# Ethernet_PHY.net
KiCad netlist of a schematic drawn in Altium Designer
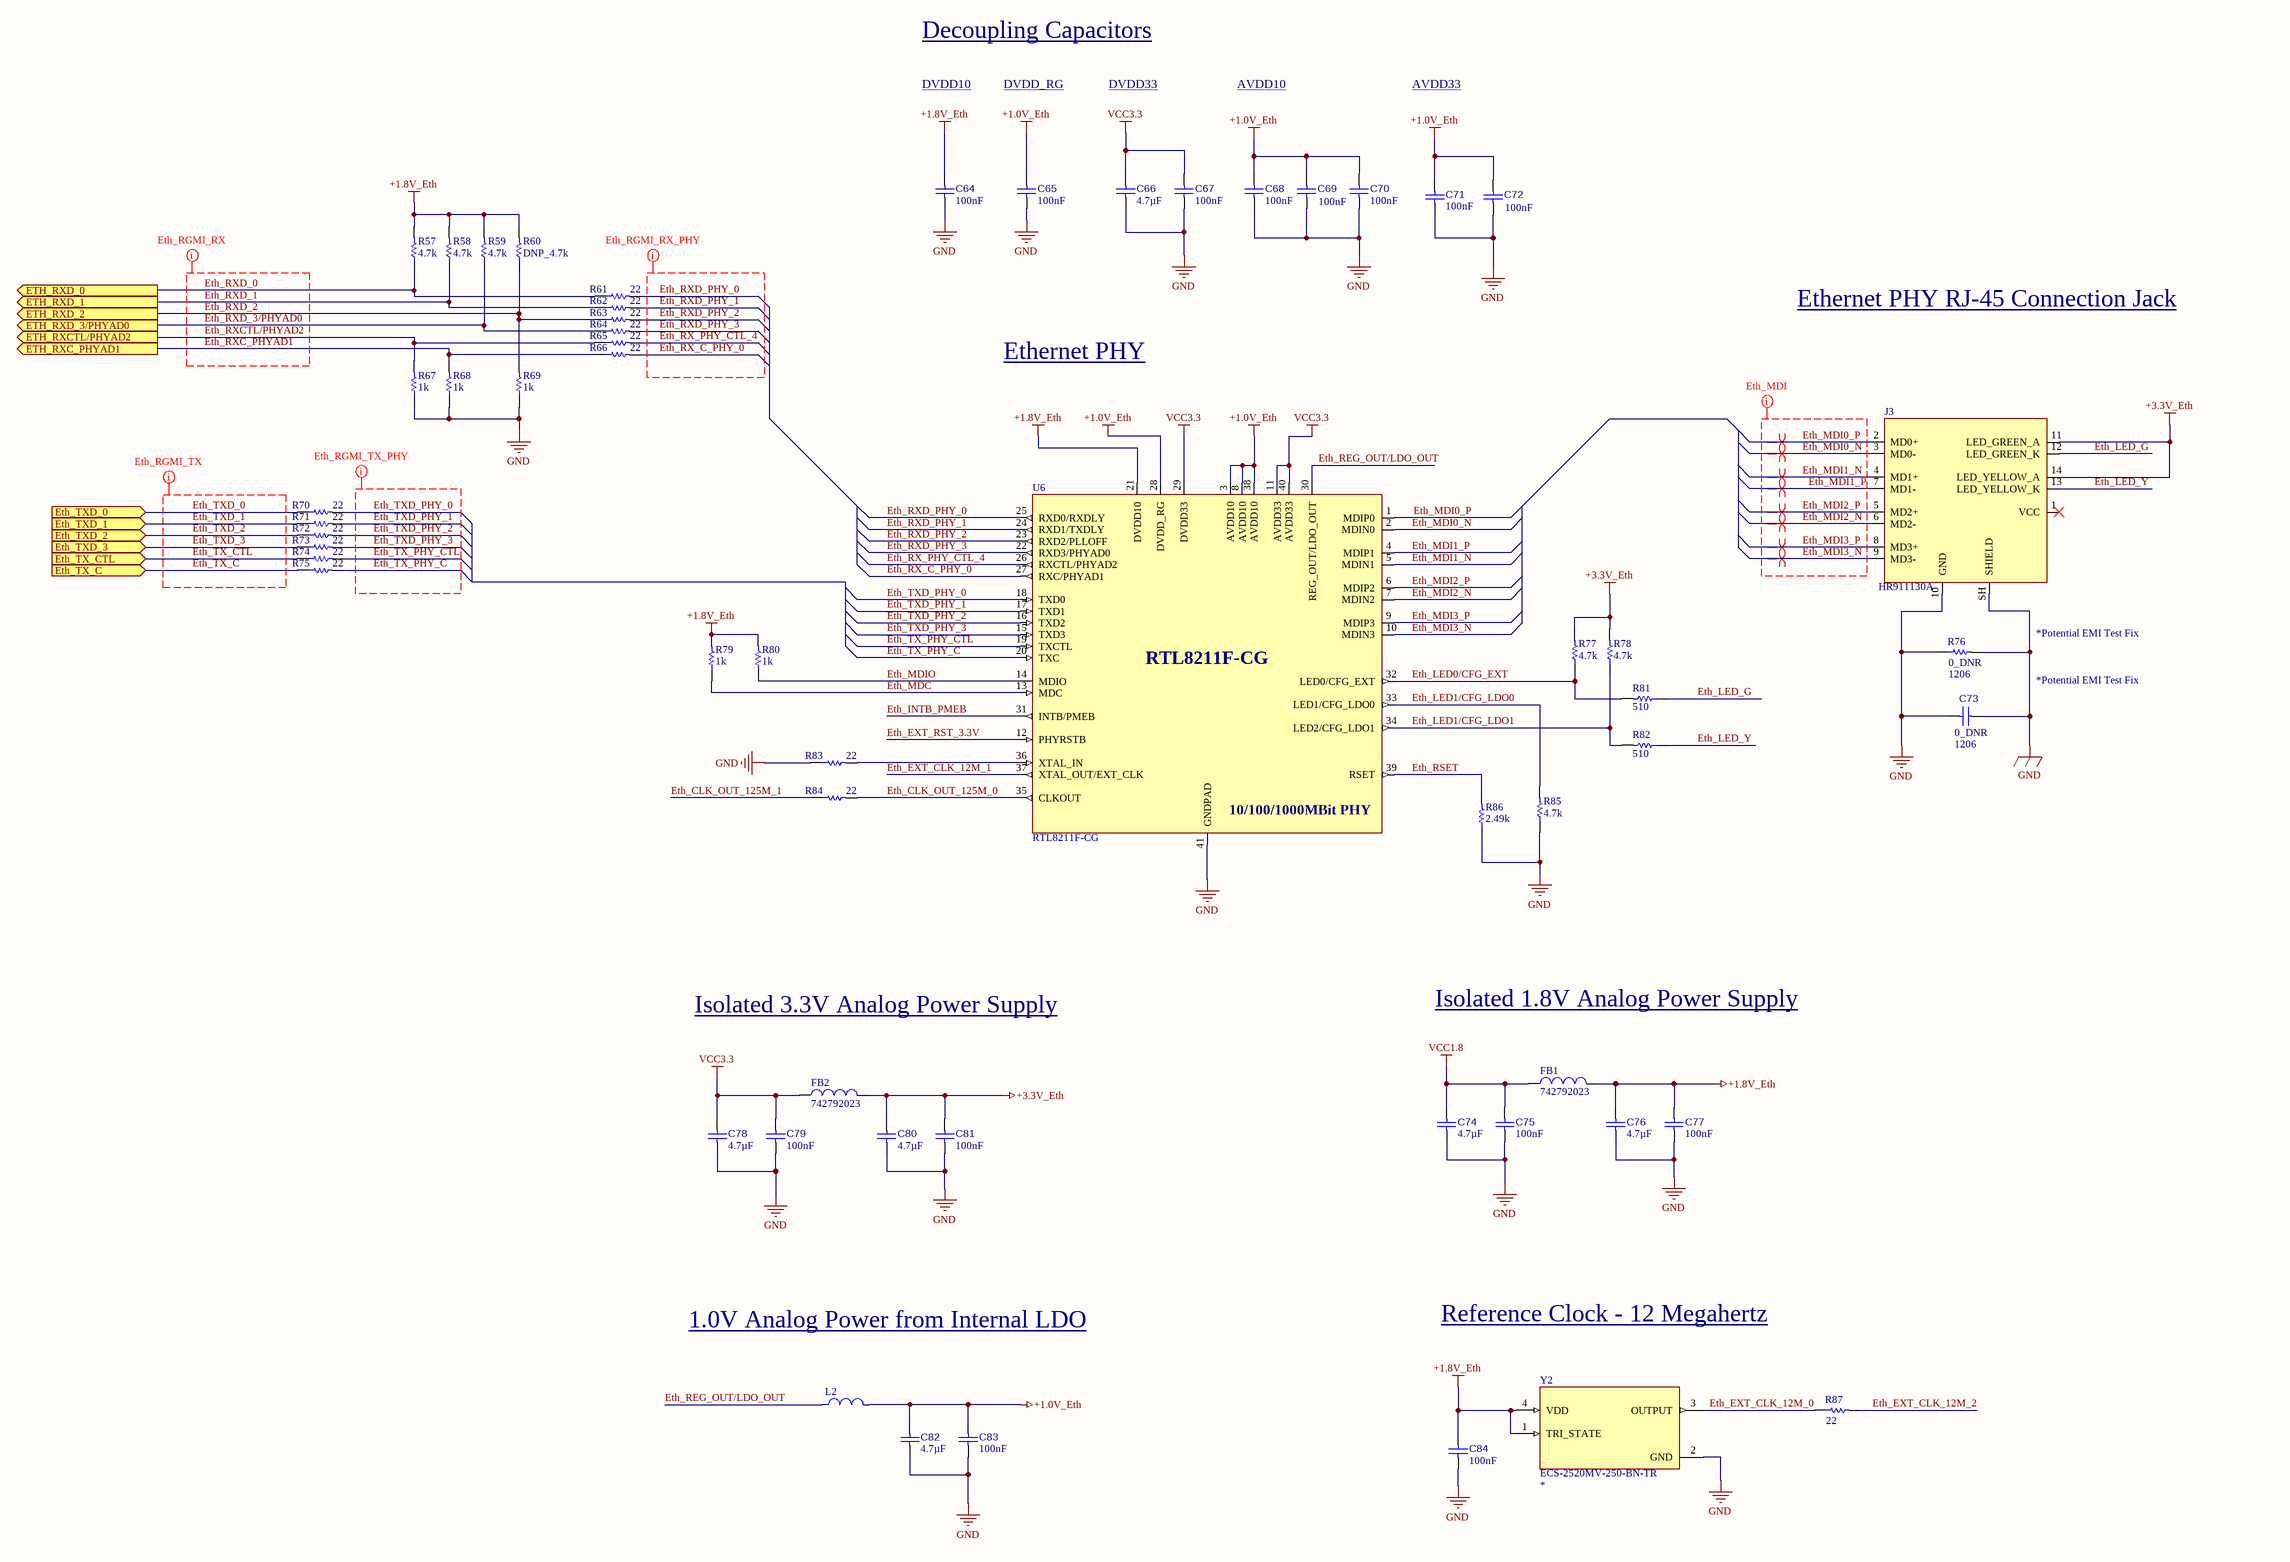
[diagram p0: Ethernet_PHY.SchDoc]

(export (version "E")
  (design (tool "Eeschema 10.0.6"))
  (components
    (comp (ref "C64")
      (value "100nF")
      (footprint "CAPC1608X90X40NL10T20")
      (description "Chip Capacitor, 100 nF, +/- 10%, 50 V, 0603 (1608 Metric)")
      (fields (field (name "TOLERANCE") "10%") (field (name "Comment") "Capacitor 100 nF +/-10% 50 V 0603"))
      (libsource (lib "Personal Workspace") (part "CAP-NP-2"))
    )
    (comp (ref "C65")
      (value "100nF")
      (footprint "CAPC1608X90X40NL10T20")
      (description "Chip Capacitor, 100 nF, +/- 10%, 50 V, 0603 (1608 Metric)")
      (fields (field (name "TOLERANCE") "10%") (field (name "Comment") "Capacitor 100 nF +/-10% 50 V 0603"))
      (libsource (lib "Personal Workspace") (part "CAP-NP-2"))
    )
    (comp (ref "C66")
      (value "4.7µF")
      (footprint "CAPC0603(1608)100_L")
      (description "Chip Capacitor, 4.7µF +/-20%, 10V, 0603, Thickness 1 mm")
      (fields (field (name "TOLERANCE") "10%") (field (name "Comment") "Capacitor 4.7µF +/-20% 10V 0603"))
      (libsource (lib "Personal Workspace") (part "CAP-NP-2"))
    )
    (comp (ref "C67")
      (value "100nF")
      (footprint "CAPC1608X90X40NL10T20")
      (description "Chip Capacitor, 100 nF, +/- 10%, 50 V, 0603 (1608 Metric)")
      (fields (field (name "TOLERANCE") "10%") (field (name "Comment") "Capacitor 100 nF +/-10% 50 V 0603"))
      (libsource (lib "Personal Workspace") (part "CAP-NP-2"))
    )
    (comp (ref "C68")
      (value "100nF")
      (footprint "CAPC1608X90X40NL10T20")
      (description "Chip Capacitor, 100 nF, +/- 10%, 50 V, 0603 (1608 Metric)")
      (fields (field (name "TOLERANCE") "10%") (field (name "Comment") "Capacitor 100 nF +/-10% 50 V 0603"))
      (libsource (lib "Personal Workspace") (part "CAP-NP-2"))
    )
    (comp (ref "C69")
      (value "100nF")
      (footprint "CAPC1608X90X40NL10T20")
      (description "Chip Capacitor, 100 nF, +/- 10%, 50 V, 0603 (1608 Metric)")
      (fields (field (name "TOLERANCE") "10%") (field (name "Comment") "Capacitor 100 nF +/-10% 50 V 0603"))
      (libsource (lib "Personal Workspace") (part "CAP-NP-2"))
    )
    (comp (ref "C70")
      (value "100nF")
      (footprint "CAPC1608X90X40NL10T20")
      (description "Chip Capacitor, 100 nF, +/- 10%, 50 V, 0603 (1608 Metric)")
      (fields (field (name "TOLERANCE") "10%") (field (name "Comment") "Capacitor 100 nF +/-10% 50 V 0603"))
      (libsource (lib "Personal Workspace") (part "CAP-NP-2"))
    )
    (comp (ref "C71")
      (value "100nF")
      (footprint "CAPC1608X90X40NL10T20")
      (description "Chip Capacitor, 100 nF, +/- 10%, 50 V, 0603 (1608 Metric)")
      (fields (field (name "TOLERANCE") "10%") (field (name "Comment") "Capacitor 100 nF +/-10% 50 V 0603"))
      (libsource (lib "Personal Workspace") (part "CAP-NP-2"))
    )
    (comp (ref "C72")
      (value "100nF")
      (footprint "CAPC1608X90X40NL10T20")
      (description "Chip Capacitor, 100 nF, +/- 10%, 50 V, 0603 (1608 Metric)")
      (fields (field (name "TOLERANCE") "10%") (field (name "Comment") "Capacitor 100 nF +/-10% 50 V 0603"))
      (libsource (lib "Personal Workspace") (part "CAP-NP-2"))
    )
    (comp (ref "C73")
      (value "0_DNR")
      (footprint "CAPC3216X180X20ML20")
      (description "Chip Capacitor, 1 uF, +/- 10%, 25 V, 1206 (3216 Metric)")
      (fields
        (field (name "CASE/PACKAGE") "1206")
        (field (name "TOLERANCE") "10%")
        (field (name "Comment") "Capacitor 1 uF +/- 10% 25 V 1206")
      )
      (libsource (lib "Personal Workspace") (part "CAP-NP-2"))
    )
    (comp (ref "C74")
      (value "4.7µF")
      (footprint "CAPC0603(1608)100_L")
      (description "Chip Capacitor, 4.7µF +/-20%, 10V, 0603, Thickness 1 mm")
      (fields (field (name "TOLERANCE") "10%") (field (name "Comment") "Capacitor 4.7µF +/-20% 10V 0603"))
      (libsource (lib "Personal Workspace") (part "CAP-NP-2"))
    )
    (comp (ref "C75")
      (value "100nF")
      (footprint "CAPC1608X90X40NL10T20")
      (description "Chip Capacitor, 100 nF, +/- 10%, 50 V, 0603 (1608 Metric)")
      (fields (field (name "TOLERANCE") "10%") (field (name "Comment") "Capacitor 100 nF +/-10% 50 V 0603"))
      (libsource (lib "Personal Workspace") (part "CAP-NP-2"))
    )
    (comp (ref "C76")
      (value "4.7µF")
      (footprint "CAPC0603(1608)100_L")
      (description "Chip Capacitor, 4.7µF +/-20%, 10V, 0603, Thickness 1 mm")
      (fields (field (name "TOLERANCE") "10%") (field (name "Comment") "Capacitor 4.7µF +/-20% 10V 0603"))
      (libsource (lib "Personal Workspace") (part "CAP-NP-2"))
    )
    (comp (ref "C77")
      (value "100nF")
      (footprint "CAPC1608X90X40NL10T20")
      (description "Chip Capacitor, 100 nF, +/- 10%, 50 V, 0603 (1608 Metric)")
      (fields (field (name "TOLERANCE") "10%") (field (name "Comment") "Capacitor 100 nF +/-10% 50 V 0603"))
      (libsource (lib "Personal Workspace") (part "CAP-NP-2"))
    )
    (comp (ref "C78")
      (value "4.7µF")
      (footprint "CAPC0603(1608)100_L")
      (description "Chip Capacitor, 4.7µF +/-20%, 10V, 0603, Thickness 1 mm")
      (fields (field (name "TOLERANCE") "10%") (field (name "Comment") "Capacitor 4.7µF +/-20% 10V 0603"))
      (libsource (lib "Personal Workspace") (part "CAP-NP-2"))
    )
    (comp (ref "C79")
      (value "100nF")
      (footprint "CAPC1608X90X40NL10T20")
      (description "Chip Capacitor, 100 nF, +/- 10%, 50 V, 0603 (1608 Metric)")
      (fields (field (name "TOLERANCE") "10%") (field (name "Comment") "Capacitor 100 nF +/-10% 50 V 0603"))
      (libsource (lib "Personal Workspace") (part "CAP-NP-2"))
    )
    (comp (ref "C80")
      (value "4.7µF")
      (footprint "CAPC0603(1608)100_L")
      (description "Chip Capacitor, 4.7µF +/-20%, 10V, 0603, Thickness 1 mm")
      (fields (field (name "TOLERANCE") "10%") (field (name "Comment") "Capacitor 4.7µF +/-20% 10V 0603"))
      (libsource (lib "Personal Workspace") (part "CAP-NP-2"))
    )
    (comp (ref "C81")
      (value "100nF")
      (footprint "CAPC1608X90X40NL10T20")
      (description "Chip Capacitor, 100 nF, +/- 10%, 50 V, 0603 (1608 Metric)")
      (fields (field (name "TOLERANCE") "10%") (field (name "Comment") "Capacitor 100 nF +/-10% 50 V 0603"))
      (libsource (lib "Personal Workspace") (part "CAP-NP-2"))
    )
    (comp (ref "C82")
      (value "4.7µF")
      (footprint "CAPC0603(1608)100_L")
      (description "Chip Capacitor, 4.7µF +/-20%, 10V, 0603, Thickness 1 mm")
      (fields (field (name "TOLERANCE") "10%") (field (name "Comment") "Capacitor 4.7µF +/-20% 10V 0603"))
      (libsource (lib "Personal Workspace") (part "CAP-NP-2"))
    )
    (comp (ref "C83")
      (value "100nF")
      (footprint "CAPC1608X90X40NL10T20")
      (description "Chip Capacitor, 100 nF, +/- 10%, 50 V, 0603 (1608 Metric)")
      (fields (field (name "TOLERANCE") "10%") (field (name "Comment") "Capacitor 100 nF +/-10% 50 V 0603"))
      (libsource (lib "Personal Workspace") (part "CAP-NP-2"))
    )
    (comp (ref "C84")
      (value "100nF")
      (footprint "CAPC1608X90X40NL10T20")
      (description "Chip Capacitor, 100 nF, +/- 10%, 50 V, 0603 (1608 Metric)")
      (fields (field (name "TOLERANCE") "10%") (field (name "Comment") "Capacitor 100 nF +/-10% 50 V 0603"))
      (libsource (lib "Personal Workspace") (part "CAP-NP-2"))
    )
    (comp (ref "FB1")
      (value "742792023")
      (footprint "WE-CBF_0805_L2W1.2H0.9_HC")
      (fields (field (name "TOLERANCE") "25%") (field (name "MANUFACTURER") "Wurth Electronics"))
      (libsource (lib "Altium Content Vault") (part "Ferrite"))
    )
    (comp (ref "FB2")
      (value "742792023")
      (footprint "WE-CBF_0805_L2W1.2H0.9_HC")
      (fields (field (name "TOLERANCE") "25%") (field (name "MANUFACTURER") "Wurth Electronics"))
      (libsource (lib "Altium Content Vault") (part "Ferrite"))
    )
    (comp (ref "J3")
      (value "HR911130A")
      (footprint "HR911130A")
      (description "100/1000Base-T Magnetics Single-Port RJ45 Connector with Integrated Magnetics and LEDs")
      (fields (field (name "MANUFACTURER") "Hanrun") (field (name "SOURCE") "Schematic-Lib-PhilsLab.SchLib"))
      (libsource (lib "Personal Workspace") (part "HR911130A"))
    )
    (comp (ref "L2")
      (value "LQM18PN3R3MGHD")
      (footprint "FP-LQM18PN_GH-MFG")
      (description "General Purpose Inductor, 3.3uH, 20%, 1 Element, Ferrite-Core, SMD, 0603")
      (fields (field (name "TOLERANCE") "20%"))
      (libsource (lib "Personal Workspace") (part "725321dda6339637d4d059423bc1c3c"))
    )
    (comp (ref "R57")
      (value "4.7k")
      (footprint "RESC1005X40X25ML05T05")
      (description "Chip Resistor, 4.7 KOhm, +/- 1%, 0.1 W, -55 to 155 degC, 0402 (1005 Metric)")
      (fields (field (name "TOLERANCE") "1%") (field (name "POWER") "100mW"))
      (libsource (lib "Personal Workspace") (part "RES"))
    )
    (comp (ref "R58")
      (value "4.7k")
      (footprint "RESC1005X40X25ML05T05")
      (description "Chip Resistor, 4.7 KOhm, +/- 1%, 0.1 W, -55 to 155 degC, 0402 (1005 Metric)")
      (fields (field (name "TOLERANCE") "1%") (field (name "POWER") "100mW"))
      (libsource (lib "Personal Workspace") (part "RES"))
    )
    (comp (ref "R59")
      (value "4.7k")
      (footprint "RESC1005X40X25ML05T05")
      (description "Chip Resistor, 4.7 KOhm, +/- 1%, 0.1 W, -55 to 155 degC, 0402 (1005 Metric)")
      (fields (field (name "TOLERANCE") "1%") (field (name "POWER") "100mW"))
      (libsource (lib "Personal Workspace") (part "RES"))
    )
    (comp (ref "R60")
      (value "DNP_4.7k")
      (footprint "RESC1005X40X25ML05T05")
      (description "Chip Resistor, 4.7 KOhm, +/- 1%, 0.1 W, -55 to 155 degC, 0402 (1005 Metric)")
      (fields (field (name "TOLERANCE") "1%") (field (name "POWER") "100mW"))
      (libsource (lib "Personal Workspace") (part "RES"))
    )
    (comp (ref "R61")
      (value "22")
      (footprint "RESC0402(1005)_L")
      (description "Chip Resistor, 22 Ohms, +/-5 %, 63 mW, -55 to 155 degC, 0402")
      (fields (field (name "POWER") "63mW") (field (name "TOLERANCE") "5%"))
      (libsource (lib "Personal Workspace") (part "RES-2"))
    )
    (comp (ref "R62")
      (value "22")
      (footprint "RESC0402(1005)_L")
      (description "Chip Resistor, 22 Ohms, +/-5 %, 63 mW, -55 to 155 degC, 0402")
      (fields (field (name "POWER") "63mW") (field (name "TOLERANCE") "5%"))
      (libsource (lib "Personal Workspace") (part "RES-2"))
    )
    (comp (ref "R63")
      (value "22")
      (footprint "RESC0402(1005)_L")
      (description "Chip Resistor, 22 Ohms, +/-5 %, 63 mW, -55 to 155 degC, 0402")
      (fields (field (name "POWER") "63mW") (field (name "TOLERANCE") "5%"))
      (libsource (lib "Personal Workspace") (part "RES-2"))
    )
    (comp (ref "R64")
      (value "22")
      (footprint "RESC0402(1005)_L")
      (description "Chip Resistor, 22 Ohms, +/-5 %, 63 mW, -55 to 155 degC, 0402")
      (fields (field (name "POWER") "63mW") (field (name "TOLERANCE") "5%"))
      (libsource (lib "Personal Workspace") (part "RES-2"))
    )
    (comp (ref "R65")
      (value "22")
      (footprint "RESC0402(1005)_L")
      (description "Chip Resistor, 22 Ohms, +/-5 %, 63 mW, -55 to 155 degC, 0402")
      (fields (field (name "POWER") "63mW") (field (name "TOLERANCE") "5%"))
      (libsource (lib "Personal Workspace") (part "RES-2"))
    )
    (comp (ref "R66")
      (value "22")
      (footprint "RESC0402(1005)_L")
      (description "Chip Resistor, 22 Ohms, +/-5 %, 63 mW, -55 to 155 degC, 0402")
      (fields (field (name "POWER") "63mW") (field (name "TOLERANCE") "5%"))
      (libsource (lib "Personal Workspace") (part "RES-2"))
    )
    (comp (ref "R67")
      (value "1k")
      (footprint "RESC1005X40X25ML05T05")
      (description "Chip Resistor, 1 KOhm, +/- 1%, 0.1 W, -55 to 155 degC, 0402 (1005 Metric)")
      (fields (field (name "POWER") "100mW") (field (name "TOLERANCE") "1%"))
      (libsource (lib "Personal Workspace") (part "RES-2"))
    )
    (comp (ref "R68")
      (value "1k")
      (footprint "RESC1005X40X25ML05T05")
      (description "Chip Resistor, 1 KOhm, +/- 1%, 0.1 W, -55 to 155 degC, 0402 (1005 Metric)")
      (fields (field (name "POWER") "100mW") (field (name "TOLERANCE") "1%"))
      (libsource (lib "Personal Workspace") (part "RES-2"))
    )
    (comp (ref "R69")
      (value "1k")
      (footprint "RESC1005X40X25ML05T05")
      (description "Chip Resistor, 1 KOhm, +/- 1%, 0.1 W, -55 to 155 degC, 0402 (1005 Metric)")
      (fields (field (name "POWER") "100mW") (field (name "TOLERANCE") "1%"))
      (libsource (lib "Personal Workspace") (part "RES-2"))
    )
    (comp (ref "R70")
      (value "22")
      (footprint "RESC0402(1005)_L")
      (description "Chip Resistor, 22 Ohms, +/-5 %, 63 mW, -55 to 155 degC, 0402")
      (fields (field (name "POWER") "63mW") (field (name "TOLERANCE") "5%"))
      (libsource (lib "Personal Workspace") (part "RES-2"))
    )
    (comp (ref "R71")
      (value "22")
      (footprint "RESC0402(1005)_L")
      (description "Chip Resistor, 22 Ohms, +/-5 %, 63 mW, -55 to 155 degC, 0402")
      (fields (field (name "POWER") "63mW") (field (name "TOLERANCE") "5%"))
      (libsource (lib "Personal Workspace") (part "RES-2"))
    )
    (comp (ref "R72")
      (value "22")
      (footprint "RESC0402(1005)_L")
      (description "Chip Resistor, 22 Ohms, +/-5 %, 63 mW, -55 to 155 degC, 0402")
      (fields (field (name "POWER") "63mW") (field (name "TOLERANCE") "5%"))
      (libsource (lib "Personal Workspace") (part "RES-2"))
    )
    (comp (ref "R73")
      (value "22")
      (footprint "RESC0402(1005)_L")
      (description "Chip Resistor, 22 Ohms, +/-5 %, 63 mW, -55 to 155 degC, 0402")
      (fields (field (name "POWER") "63mW") (field (name "TOLERANCE") "5%"))
      (libsource (lib "Personal Workspace") (part "RES-2"))
    )
    (comp (ref "R74")
      (value "22")
      (footprint "RESC0402(1005)_L")
      (description "Chip Resistor, 22 Ohms, +/-5 %, 63 mW, -55 to 155 degC, 0402")
      (fields (field (name "POWER") "63mW") (field (name "TOLERANCE") "5%"))
      (libsource (lib "Personal Workspace") (part "RES-2"))
    )
    (comp (ref "R75")
      (value "22")
      (footprint "RESC0402(1005)_L")
      (description "Chip Resistor, 22 Ohms, +/-5 %, 63 mW, -55 to 155 degC, 0402")
      (fields (field (name "POWER") "63mW") (field (name "TOLERANCE") "5%"))
      (libsource (lib "Personal Workspace") (part "RES-2"))
    )
    (comp (ref "R76")
      (value "0_DNR")
      (footprint "RESC3116X70X50ML13T20")
      (description "Chip Resistor, 0 Ohm, 0.25 W, -55 to 155 degC, 1206 (3216 Metric)")
      (fields
        (field (name "TOLERANCE") "0.05%")
        (field (name "CASE/PACKAGE") "1206")
        (field (name "Comment") "Resistor 0R +/- 0.05% 1206 250 mW")
      )
      (libsource (lib "Personal Workspace") (part "RES-2"))
    )
    (comp (ref "R77")
      (value "4.7k")
      (footprint "RESC1005X40X25ML05T05")
      (description "Chip Resistor, 4.7 KOhm, +/- 1%, 0.1 W, -55 to 155 degC, 0402 (1005 Metric)")
      (fields (field (name "TOLERANCE") "1%") (field (name "POWER") "100mW"))
      (libsource (lib "Personal Workspace") (part "RES"))
    )
    (comp (ref "R78")
      (value "4.7k")
      (footprint "RESC1005X40X25ML05T05")
      (description "Chip Resistor, 4.7 KOhm, +/- 1%, 0.1 W, -55 to 155 degC, 0402 (1005 Metric)")
      (fields (field (name "TOLERANCE") "1%") (field (name "POWER") "100mW"))
      (libsource (lib "Personal Workspace") (part "RES"))
    )
    (comp (ref "R79")
      (value "1k")
      (footprint "RESC1005X40X25ML05T05")
      (description "Chip Resistor, 1 KOhm, +/- 1%, 0.1 W, -55 to 155 degC, 0402 (1005 Metric)")
      (fields (field (name "POWER") "100mW") (field (name "TOLERANCE") "1%"))
      (libsource (lib "Personal Workspace") (part "RES-2"))
    )
    (comp (ref "R80")
      (value "1k")
      (footprint "RESC1005X40X25ML05T05")
      (description "Chip Resistor, 1 KOhm, +/- 1%, 0.1 W, -55 to 155 degC, 0402 (1005 Metric)")
      (fields (field (name "POWER") "100mW") (field (name "TOLERANCE") "1%"))
      (libsource (lib "Personal Workspace") (part "RES-2"))
    )
    (comp (ref "R81")
      (value "510")
      (footprint "RESC1005X40X25NL05T10")
      (fields
        (field (name "POWER") "62.5mW")
        (field (name "TOLERANCE") "1%")
        (field (name "Comment") "RC0402FR-07510RL")
      )
      (libsource (lib "Personal Workspace") (part "RES"))
    )
    (comp (ref "R82")
      (value "510")
      (footprint "RESC1005X40X25NL05T10")
      (fields
        (field (name "POWER") "62.5mW")
        (field (name "TOLERANCE") "1%")
        (field (name "Comment") "RC0402FR-07510RL")
      )
      (libsource (lib "Personal Workspace") (part "RES"))
    )
    (comp (ref "R83")
      (value "22")
      (footprint "RESC0402(1005)_L")
      (description "Chip Resistor, 22 Ohms, +/-5 %, 63 mW, -55 to 155 degC, 0402")
      (fields (field (name "POWER") "63mW") (field (name "TOLERANCE") "5%"))
      (libsource (lib "Personal Workspace") (part "RES-2"))
    )
    (comp (ref "R84")
      (value "22")
      (footprint "RESC0402(1005)_L")
      (description "Chip Resistor, 22 Ohms, +/-5 %, 63 mW, -55 to 155 degC, 0402")
      (fields (field (name "POWER") "63mW") (field (name "TOLERANCE") "5%"))
      (libsource (lib "Personal Workspace") (part "RES-2"))
    )
    (comp (ref "R85")
      (value "4.7k")
      (footprint "RESC1005X40X25ML05T05")
      (description "Chip Resistor, 4.7 KOhm, +/- 1%, 0.1 W, -55 to 155 degC, 0402 (1005 Metric)")
      (fields (field (name "TOLERANCE") "1%") (field (name "POWER") "100mW"))
      (libsource (lib "Personal Workspace") (part "RES"))
    )
    (comp (ref "R86")
      (value "2.49k")
      (footprint "RESC1005X40X25NL05T10")
      (fields
        (field (name "TOLERANCE") "1%")
        (field (name "POWER") "62.5mW")
        (field (name "Comment") "RC0402FR-072K49L")
      )
      (libsource (lib "Personal Workspace") (part "RES"))
    )
    (comp (ref "R87")
      (value "22")
      (footprint "RESC0402(1005)_L")
      (description "Chip Resistor, 22 Ohms, +/-5 %, 63 mW, -55 to 155 degC, 0402")
      (fields (field (name "POWER") "63mW") (field (name "TOLERANCE") "5%"))
      (libsource (lib "Personal Workspace") (part "RES-2"))
    )
    (comp (ref "U6")
      (value "RTL8211F-CG")
      (footprint "QFN-40-0.4-EP")
      (description "INTEGRATED 10/100/1000M ETHERNET PRECISION TRANSCEIVER")
      (fields (field (name "MANUFACTURER") "Realtek") (field (name "SOURCE") "Schematic-Lib-PhilsLab.SchLib"))
      (libsource (lib "Personal Workspace") (part "RTL8211F-CG"))
    )
    (comp (ref "Y2")
      (value "ECS-2520MV-250-BN-TR")
      (footprint "OSC_ECS-2520S25-250-FN-TR")
      (description "25 MHz XO (Standard) HCMOS Oscillator 1.6V ~ 3.6V Enable/Disable 4-SMD, No Lead")
      (fields (field (name "ALTIUM_VALUE") "*") (field (name "MF") "ECS Inc."))
      (libsource (lib "Personal Workspace") (part "ECS-2520MV-250-BN-TR"))
    )
  )
  (nets
    (net (code "1") (name "+1.0V_Eth") (class "Default")
      (node (ref "C65") (pin "2") (pinfunction "2_2") (pintype "passive"))
      (node (ref "C68") (pin "2") (pinfunction "2_2") (pintype "passive"))
      (node (ref "C69") (pin "2") (pinfunction "2_2") (pintype "passive"))
      (node (ref "C70") (pin "2") (pinfunction "2_2") (pintype "passive"))
      (node (ref "C71") (pin "2") (pinfunction "2_2") (pintype "passive"))
      (node (ref "C72") (pin "2") (pinfunction "2_2") (pintype "passive"))
      (node (ref "C82") (pin "2") (pinfunction "2_2") (pintype "passive"))
      (node (ref "C83") (pin "2") (pinfunction "2_2") (pintype "passive"))
      (node (ref "L2") (pin "2") (pinfunction "2_2") (pintype "passive"))
      (node (ref "U6") (pin "28") (pinfunction "DVDD_RG_28") (pintype "power_in"))
      (node (ref "U6") (pin "3") (pinfunction "AVDD10_3") (pintype "power_in"))
      (node (ref "U6") (pin "38") (pinfunction "AVDD10_38") (pintype "power_in"))
      (node (ref "U6") (pin "8") (pinfunction "AVDD10_8") (pintype "power_in"))
    )
    (net (code "2") (name "+1.8V_Eth") (class "Default")
      (node (ref "C64") (pin "2") (pinfunction "2_2") (pintype "passive"))
      (node (ref "C76") (pin "2") (pinfunction "2_2") (pintype "passive"))
      (node (ref "C77") (pin "2") (pinfunction "2_2") (pintype "passive"))
      (node (ref "C84") (pin "2") (pinfunction "2_2") (pintype "passive"))
      (node (ref "FB1") (pin "2") (pinfunction "2_2") (pintype "passive"))
      (node (ref "R57") (pin "2") (pinfunction "2_2") (pintype "passive"))
      (node (ref "R58") (pin "2") (pinfunction "2_2") (pintype "passive"))
      (node (ref "R59") (pin "2") (pinfunction "2_2") (pintype "passive"))
      (node (ref "R60") (pin "2") (pinfunction "2_2") (pintype "passive"))
      (node (ref "R79") (pin "2") (pinfunction "2_2") (pintype "passive"))
      (node (ref "R80") (pin "2") (pinfunction "2_2") (pintype "passive"))
      (node (ref "U6") (pin "21") (pinfunction "DVDD10_21") (pintype "power_in"))
      (node (ref "Y2") (pin "1") (pinfunction "TRI_STATE_1") (pintype "input"))
      (node (ref "Y2") (pin "4") (pinfunction "VDD_4") (pintype "input"))
    )
    (net (code "3") (name "+3.3V_Eth") (class "Default")
      (node (ref "C80") (pin "2") (pinfunction "2_2") (pintype "passive"))
      (node (ref "C81") (pin "2") (pinfunction "2_2") (pintype "passive"))
      (node (ref "FB2") (pin "2") (pinfunction "2_2") (pintype "passive"))
      (node (ref "J3") (pin "11") (pinfunction "LED_GREEN_A_11") (pintype "passive"))
      (node (ref "J3") (pin "14") (pinfunction "LED_YELLOW_A_14") (pintype "passive"))
      (node (ref "R77") (pin "2") (pinfunction "2_2") (pintype "passive"))
      (node (ref "R78") (pin "2") (pinfunction "2_2") (pintype "passive"))
    )
    (net (code "4") (name "/Eth_CLK_OUT_125M_0") (class "Default")
      (node (ref "R84") (pin "2") (pinfunction "2_2") (pintype "passive"))
      (node (ref "U6") (pin "35") (pinfunction "CLKOUT_35") (pintype "output"))
    )
    (net (code "5") (name "/Eth_CLK_OUT_125M_1") (class "Default")
      (node (ref "R84") (pin "1") (pinfunction "1_1") (pintype "passive"))
    )
    (net (code "6") (name "/Eth_EXT_CLK_12M_0") (class "Default")
      (node (ref "R87") (pin "1") (pinfunction "1_1") (pintype "passive"))
      (node (ref "Y2") (pin "3") (pinfunction "OUTPUT_3") (pintype "output"))
    )
    (net (code "7") (name "/Eth_EXT_CLK_12M_1") (class "Default")
      (node (ref "U6") (pin "37") (pinfunction "XTAL_OUT/EXT_CLK_37") (pintype "output"))
    )
    (net (code "8") (name "/Eth_EXT_CLK_12M_2") (class "Default")
      (node (ref "R87") (pin "2") (pinfunction "2_2") (pintype "passive"))
    )
    (net (code "9") (name "/Eth_EXT_RST_3.3V") (class "Default")
      (node (ref "U6") (pin "12") (pinfunction "PHYRSTB_12") (pintype "input"))
    )
    (net (code "10") (name "/Eth_INTB_PMEB") (class "Default")
      (node (ref "U6") (pin "31") (pinfunction "INTB/PMEB_31") (pintype "output"))
    )
    (net (code "11") (name "/Eth_LED0{slash}CFG_EXT") (class "Default")
      (node (ref "R77") (pin "1") (pinfunction "1_1") (pintype "passive"))
      (node (ref "R81") (pin "2") (pinfunction "2_2") (pintype "passive"))
      (node (ref "U6") (pin "32") (pinfunction "LED0/CFG_EXT_32") (pintype "output"))
    )
    (net (code "12") (name "/Eth_LED1{slash}CFG_LDO0") (class "Default")
      (node (ref "R85") (pin "2") (pinfunction "2_2") (pintype "passive"))
      (node (ref "U6") (pin "33") (pinfunction "LED1/CFG_LDO0_33") (pintype "output"))
    )
    (net (code "13") (name "/Eth_LED1{slash}CFG_LDO1") (class "Default")
      (node (ref "R78") (pin "1") (pinfunction "1_1") (pintype "passive"))
      (node (ref "R82") (pin "2") (pinfunction "2_2") (pintype "passive"))
      (node (ref "U6") (pin "34") (pinfunction "LED2/CFG_LDO1_34") (pintype "output"))
    )
    (net (code "14") (name "/Eth_LED_G") (class "Default")
      (node (ref "J3") (pin "12") (pinfunction "LED_GREEN_K_12") (pintype "passive"))
      (node (ref "R81") (pin "1") (pinfunction "1_1") (pintype "passive"))
    )
    (net (code "15") (name "/Eth_LED_Y") (class "Default")
      (node (ref "J3") (pin "13") (pinfunction "LED_YELLOW_K_13") (pintype "passive"))
      (node (ref "R82") (pin "1") (pinfunction "1_1") (pintype "passive"))
    )
    (net (code "16") (name "/Eth_MDC") (class "Default")
      (node (ref "R79") (pin "1") (pinfunction "1_1") (pintype "passive"))
      (node (ref "U6") (pin "13") (pinfunction "MDC_13") (pintype "input"))
    )
    (net (code "17") (name "/Eth_MDI0_N") (class "Default")
      (node (ref "J3") (pin "3") (pinfunction "MD0-_3") (pintype "passive"))
      (node (ref "U6") (pin "2") (pinfunction "MDIN0_2") (pintype "bidirectional"))
    )
    (net (code "18") (name "/Eth_MDI0_P") (class "Default")
      (node (ref "J3") (pin "2") (pinfunction "MD0+_2") (pintype "passive"))
      (node (ref "U6") (pin "1") (pinfunction "MDIP0_1") (pintype "bidirectional"))
    )
    (net (code "19") (name "/Eth_MDI1_N") (class "Default")
      (node (ref "J3") (pin "4") (pinfunction "MD1+_4") (pintype "passive"))
      (node (ref "U6") (pin "5") (pinfunction "MDIN1_5") (pintype "bidirectional"))
    )
    (net (code "20") (name "/Eth_MDI1_P") (class "Default")
      (node (ref "J3") (pin "7") (pinfunction "MD1-_7") (pintype "passive"))
      (node (ref "U6") (pin "4") (pinfunction "MDIP1_4") (pintype "bidirectional"))
    )
    (net (code "21") (name "/Eth_MDI2_N") (class "Default")
      (node (ref "J3") (pin "6") (pinfunction "MD2-_6") (pintype "passive"))
      (node (ref "U6") (pin "7") (pinfunction "MDIN2_7") (pintype "bidirectional"))
    )
    (net (code "22") (name "/Eth_MDI2_P") (class "Default")
      (node (ref "J3") (pin "5") (pinfunction "MD2+_5") (pintype "passive"))
      (node (ref "U6") (pin "6") (pinfunction "MDIP2_6") (pintype "bidirectional"))
    )
    (net (code "23") (name "/Eth_MDI3_N") (class "Default")
      (node (ref "J3") (pin "9") (pinfunction "MD3-_9") (pintype "passive"))
      (node (ref "U6") (pin "10") (pinfunction "MDIN3_10") (pintype "bidirectional"))
    )
    (net (code "24") (name "/Eth_MDI3_P") (class "Default")
      (node (ref "J3") (pin "8") (pinfunction "MD3+_8") (pintype "passive"))
      (node (ref "U6") (pin "9") (pinfunction "MDIP3_9") (pintype "bidirectional"))
    )
    (net (code "25") (name "/Eth_MDIO") (class "Default")
      (node (ref "R80") (pin "1") (pinfunction "1_1") (pintype "passive"))
      (node (ref "U6") (pin "14") (pinfunction "MDIO_14") (pintype "bidirectional"))
    )
    (net (code "26") (name "/Eth_REG_OUT{slash}LDO_OUT") (class "Default")
      (node (ref "L2") (pin "1") (pinfunction "1_1") (pintype "passive"))
      (node (ref "U6") (pin "30") (pinfunction "REG_OUT/LDO_OUT_30") (pintype "power_in"))
    )
    (net (code "27") (name "/Eth_RSET") (class "Default")
      (node (ref "R86") (pin "2") (pinfunction "2_2") (pintype "passive"))
      (node (ref "U6") (pin "39") (pinfunction "RSET_39") (pintype "output"))
    )
    (net (code "28") (name "/Eth_RXCTL{slash}PHYAD2") (class "Default")
      (node (ref "R65") (pin "1") (pinfunction "1_1") (pintype "passive"))
      (node (ref "R67") (pin "2") (pinfunction "2_2") (pintype "passive"))
    )
    (net (code "29") (name "/Eth_RXC_PHYAD1") (class "Default")
      (node (ref "R66") (pin "1") (pinfunction "1_1") (pintype "passive"))
      (node (ref "R68") (pin "2") (pinfunction "2_2") (pintype "passive"))
    )
    (net (code "30") (name "/Eth_RXD_0") (class "Default")
      (node (ref "R57") (pin "1") (pinfunction "1_1") (pintype "passive"))
      (node (ref "R61") (pin "1") (pinfunction "1_1") (pintype "passive"))
    )
    (net (code "31") (name "/Eth_RXD_1") (class "Default")
      (node (ref "R58") (pin "1") (pinfunction "1_1") (pintype "passive"))
      (node (ref "R62") (pin "1") (pinfunction "1_1") (pintype "passive"))
    )
    (net (code "32") (name "/Eth_RXD_2") (class "Default")
      (node (ref "R60") (pin "1") (pinfunction "1_1") (pintype "passive"))
      (node (ref "R63") (pin "1") (pinfunction "1_1") (pintype "passive"))
      (node (ref "R69") (pin "2") (pinfunction "2_2") (pintype "passive"))
    )
    (net (code "33") (name "/Eth_RXD_3{slash}PHYAD0") (class "Default")
      (node (ref "R59") (pin "1") (pinfunction "1_1") (pintype "passive"))
      (node (ref "R64") (pin "1") (pinfunction "1_1") (pintype "passive"))
    )
    (net (code "34") (name "/Eth_RXD_PHY_0") (class "Default")
      (node (ref "R61") (pin "2") (pinfunction "2_2") (pintype "passive"))
      (node (ref "U6") (pin "25") (pinfunction "RXD0/RXDLY_25") (pintype "output"))
    )
    (net (code "35") (name "/Eth_RXD_PHY_1") (class "Default")
      (node (ref "R62") (pin "2") (pinfunction "2_2") (pintype "passive"))
      (node (ref "U6") (pin "24") (pinfunction "RXD1/TXDLY_24") (pintype "output"))
    )
    (net (code "36") (name "/Eth_RXD_PHY_2") (class "Default")
      (node (ref "R63") (pin "2") (pinfunction "2_2") (pintype "passive"))
      (node (ref "U6") (pin "23") (pinfunction "RXD2/PLLOFF_23") (pintype "output"))
    )
    (net (code "37") (name "/Eth_RXD_PHY_3") (class "Default")
      (node (ref "R64") (pin "2") (pinfunction "2_2") (pintype "passive"))
      (node (ref "U6") (pin "22") (pinfunction "RXD3/PHYAD0_22") (pintype "output"))
    )
    (net (code "38") (name "/Eth_RX_C_PHY_0") (class "Default")
      (node (ref "R66") (pin "2") (pinfunction "2_2") (pintype "passive"))
      (node (ref "U6") (pin "27") (pinfunction "RXC/PHYAD1_27") (pintype "output"))
    )
    (net (code "39") (name "/Eth_RX_PHY_CTL_4") (class "Default")
      (node (ref "R65") (pin "2") (pinfunction "2_2") (pintype "passive"))
      (node (ref "U6") (pin "26") (pinfunction "RXCTL/PHYAD2_26") (pintype "output"))
    )
    (net (code "40") (name "/Eth_TXD_0") (class "Default")
      (node (ref "R70") (pin "1") (pinfunction "1_1") (pintype "passive"))
    )
    (net (code "41") (name "/Eth_TXD_1") (class "Default")
      (node (ref "R71") (pin "1") (pinfunction "1_1") (pintype "passive"))
    )
    (net (code "42") (name "/Eth_TXD_2") (class "Default")
      (node (ref "R72") (pin "1") (pinfunction "1_1") (pintype "passive"))
    )
    (net (code "43") (name "/Eth_TXD_3") (class "Default")
      (node (ref "R73") (pin "1") (pinfunction "1_1") (pintype "passive"))
    )
    (net (code "44") (name "/Eth_TXD_PHY_0") (class "Default")
      (node (ref "R70") (pin "2") (pinfunction "2_2") (pintype "passive"))
      (node (ref "U6") (pin "18") (pinfunction "TXD0_18") (pintype "input"))
    )
    (net (code "45") (name "/Eth_TXD_PHY_1") (class "Default")
      (node (ref "R71") (pin "2") (pinfunction "2_2") (pintype "passive"))
      (node (ref "U6") (pin "17") (pinfunction "TXD1_17") (pintype "input"))
    )
    (net (code "46") (name "/Eth_TXD_PHY_2") (class "Default")
      (node (ref "R72") (pin "2") (pinfunction "2_2") (pintype "passive"))
      (node (ref "U6") (pin "16") (pinfunction "TXD2_16") (pintype "input"))
    )
    (net (code "47") (name "/Eth_TXD_PHY_3") (class "Default")
      (node (ref "R73") (pin "2") (pinfunction "2_2") (pintype "passive"))
      (node (ref "U6") (pin "15") (pinfunction "TXD3_15") (pintype "input"))
    )
    (net (code "48") (name "/Eth_TX_C") (class "Default")
      (node (ref "R75") (pin "1") (pinfunction "1_1") (pintype "passive"))
    )
    (net (code "49") (name "/Eth_TX_CTL") (class "Default")
      (node (ref "R74") (pin "1") (pinfunction "1_1") (pintype "passive"))
    )
    (net (code "50") (name "/Eth_TX_PHY_C") (class "Default")
      (node (ref "R75") (pin "2") (pinfunction "2_2") (pintype "passive"))
      (node (ref "U6") (pin "20") (pinfunction "TXC_20") (pintype "input"))
    )
    (net (code "51") (name "/Eth_TX_PHY_CTL") (class "Default")
      (node (ref "R74") (pin "2") (pinfunction "2_2") (pintype "passive"))
      (node (ref "U6") (pin "19") (pinfunction "TXCTL_19") (pintype "input"))
    )
    (net (code "52") (name "GND") (class "Default")
      (node (ref "C64") (pin "1") (pinfunction "1_1") (pintype "passive"))
      (node (ref "C65") (pin "1") (pinfunction "1_1") (pintype "passive"))
      (node (ref "C66") (pin "1") (pinfunction "1_1") (pintype "passive"))
      (node (ref "C67") (pin "1") (pinfunction "1_1") (pintype "passive"))
      (node (ref "C68") (pin "1") (pinfunction "1_1") (pintype "passive"))
      (node (ref "C69") (pin "1") (pinfunction "1_1") (pintype "passive"))
      (node (ref "C70") (pin "1") (pinfunction "1_1") (pintype "passive"))
      (node (ref "C71") (pin "1") (pinfunction "1_1") (pintype "passive"))
      (node (ref "C72") (pin "1") (pinfunction "1_1") (pintype "passive"))
      (node (ref "C73") (pin "1") (pinfunction "1_1") (pintype "passive"))
      (node (ref "C73") (pin "2") (pinfunction "2_2") (pintype "passive"))
      (node (ref "C74") (pin "1") (pinfunction "1_1") (pintype "passive"))
      (node (ref "C75") (pin "1") (pinfunction "1_1") (pintype "passive"))
      (node (ref "C76") (pin "1") (pinfunction "1_1") (pintype "passive"))
      (node (ref "C77") (pin "1") (pinfunction "1_1") (pintype "passive"))
      (node (ref "C78") (pin "1") (pinfunction "1_1") (pintype "passive"))
      (node (ref "C79") (pin "1") (pinfunction "1_1") (pintype "passive"))
      (node (ref "C80") (pin "1") (pinfunction "1_1") (pintype "passive"))
      (node (ref "C81") (pin "1") (pinfunction "1_1") (pintype "passive"))
      (node (ref "C82") (pin "1") (pinfunction "1_1") (pintype "passive"))
      (node (ref "C83") (pin "1") (pinfunction "1_1") (pintype "passive"))
      (node (ref "C84") (pin "1") (pinfunction "1_1") (pintype "passive"))
      (node (ref "J3") (pin "10") (pinfunction "GND_10") (pintype "passive"))
      (node (ref "J3") (pin "SH") (pinfunction "SHIELD_SH") (pintype "passive"))
      (node (ref "R67") (pin "1") (pinfunction "1_1") (pintype "passive"))
      (node (ref "R68") (pin "1") (pinfunction "1_1") (pintype "passive"))
      (node (ref "R69") (pin "1") (pinfunction "1_1") (pintype "passive"))
      (node (ref "R76") (pin "1") (pinfunction "1_1") (pintype "passive"))
      (node (ref "R76") (pin "2") (pinfunction "2_2") (pintype "passive"))
      (node (ref "R83") (pin "1") (pinfunction "1_1") (pintype "passive"))
      (node (ref "R85") (pin "1") (pinfunction "1_1") (pintype "passive"))
      (node (ref "R86") (pin "1") (pinfunction "1_1") (pintype "passive"))
      (node (ref "U6") (pin "41") (pinfunction "GNDPAD_41") (pintype "power_in"))
      (node (ref "Y2") (pin "2") (pinfunction "GND_2") (pintype "power_in"))
    )
    (net (code "53") (name "Net-(U6-XTAL_IN)") (class "Default")
      (node (ref "R83") (pin "2") (pinfunction "2_2") (pintype "passive"))
      (node (ref "U6") (pin "36") (pinfunction "XTAL_IN_36") (pintype "input"))
    )
    (net (code "54") (name "VCC1.8") (class "Default")
      (node (ref "C74") (pin "2") (pinfunction "2_2") (pintype "passive"))
      (node (ref "C75") (pin "2") (pinfunction "2_2") (pintype "passive"))
      (node (ref "FB1") (pin "1") (pinfunction "1_1") (pintype "passive"))
    )
    (net (code "55") (name "VCC3.3") (class "Default")
      (node (ref "C66") (pin "2") (pinfunction "2_2") (pintype "passive"))
      (node (ref "C67") (pin "2") (pinfunction "2_2") (pintype "passive"))
      (node (ref "C78") (pin "2") (pinfunction "2_2") (pintype "passive"))
      (node (ref "C79") (pin "2") (pinfunction "2_2") (pintype "passive"))
      (node (ref "FB2") (pin "1") (pinfunction "1_1") (pintype "passive"))
      (node (ref "U6") (pin "11") (pinfunction "AVDD33_11") (pintype "power_in"))
      (node (ref "U6") (pin "29") (pinfunction "DVDD33_29") (pintype "power_in"))
      (node (ref "U6") (pin "40") (pinfunction "AVDD33_40") (pintype "power_in"))
    )
    (net (code "56") (name "unconnected-(J3-VCC-Pad1)") (class "Default")
      (node (ref "J3") (pin "1") (pinfunction "VCC_1") (pintype "passive+no_connect"))
    )
  )
)
